# power_supply.net
KiCad netlist of a schematic drawn in EAGLE
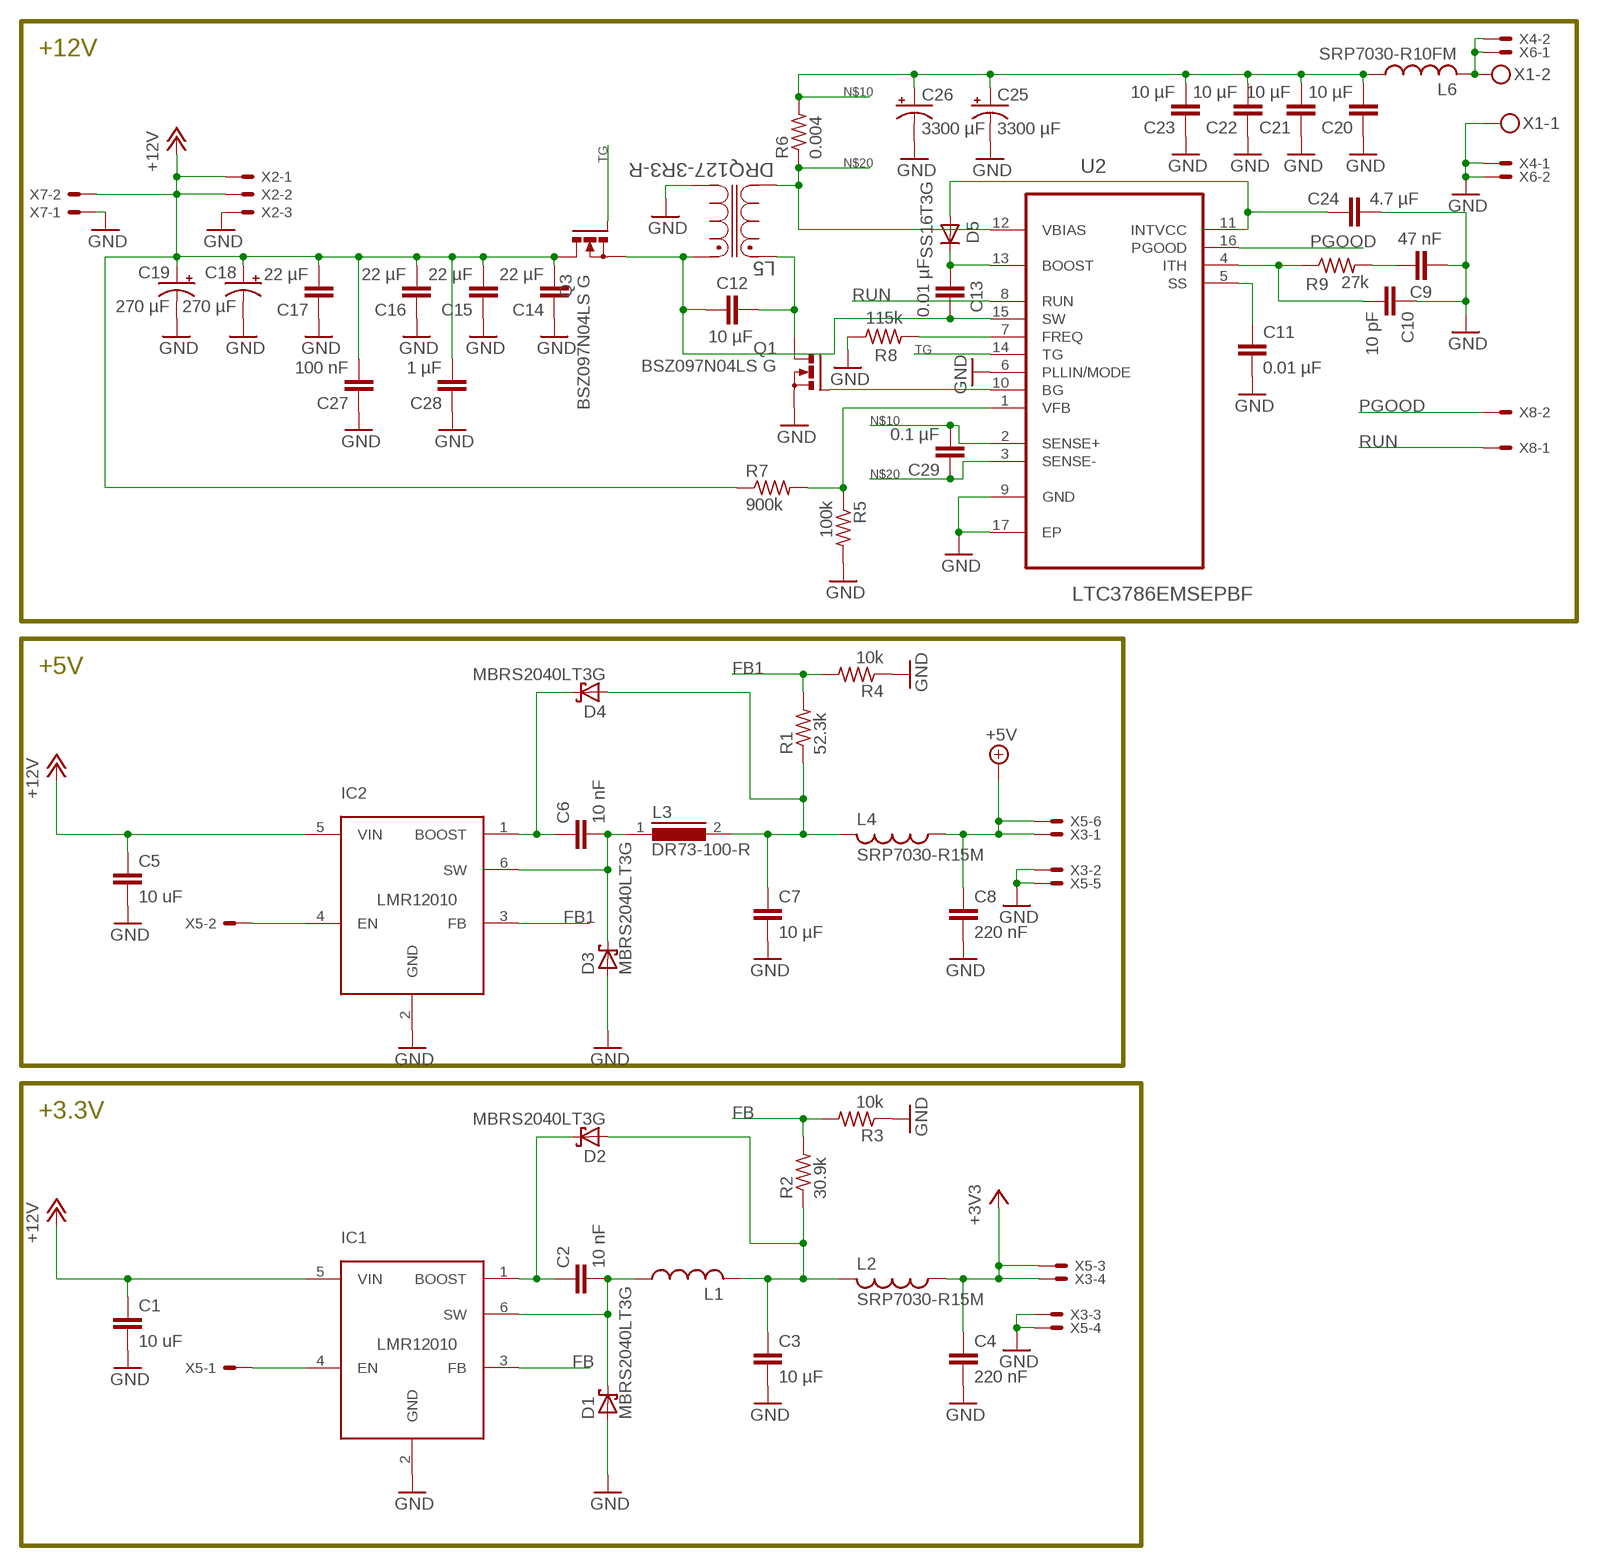
[diagram p0: schematic, sheet 1]

(export (version "E")
  (design (tool "Eeschema 10.0.6"))
  (components
    (comp (ref "C1")
      (value "10 uF")
      (footprint "eagle-import:C0805")
      (libsource (lib "eagle-import") (part "C-EUC0805"))
    )
    (comp (ref "C2")
      (value "10 nF")
      (footprint "eagle-import:C0805")
      (libsource (lib "eagle-import") (part "C-EUC0805"))
    )
    (comp (ref "C3")
      (value "10 µF")
      (footprint "eagle-import:C0805")
      (libsource (lib "eagle-import") (part "C-EUC0805"))
    )
    (comp (ref "C4")
      (value "220 nF")
      (footprint "eagle-import:C0805")
      (libsource (lib "eagle-import") (part "C-EUC0805"))
    )
    (comp (ref "C5")
      (value "10 uF")
      (footprint "eagle-import:C0805")
      (libsource (lib "eagle-import") (part "C-EUC0805"))
    )
    (comp (ref "C6")
      (value "10 nF")
      (footprint "eagle-import:C0805")
      (libsource (lib "eagle-import") (part "C-EUC0805"))
    )
    (comp (ref "C7")
      (value "10 µF")
      (footprint "eagle-import:C0805")
      (libsource (lib "eagle-import") (part "C-EUC0805"))
    )
    (comp (ref "C8")
      (value "220 nF")
      (footprint "eagle-import:C0805")
      (libsource (lib "eagle-import") (part "C-EUC0805"))
    )
    (comp (ref "C9")
      (value "47 nF")
      (footprint "eagle-import:C0805")
      (libsource (lib "eagle-import") (part "C-EUC0805"))
    )
    (comp (ref "C10")
      (value "10 pF")
      (footprint "eagle-import:C0805")
      (libsource (lib "eagle-import") (part "C-EUC0805"))
    )
    (comp (ref "C11")
      (value "0.01 µF")
      (footprint "eagle-import:C0805")
      (libsource (lib "eagle-import") (part "C-EUC0805"))
    )
    (comp (ref "C12")
      (value "10 µF")
      (footprint "eagle-import:C1210")
      (libsource (lib "eagle-import") (part "C-EUC1210"))
    )
    (comp (ref "C13")
      (value "0.01 µF")
      (footprint "eagle-import:C0805")
      (libsource (lib "eagle-import") (part "C-EUC0805"))
    )
    (comp (ref "C14")
      (value "22 µF")
      (footprint "eagle-import:C1210")
      (libsource (lib "eagle-import") (part "C-EUC1210"))
    )
    (comp (ref "C15")
      (value "22 µF")
      (footprint "eagle-import:C1210")
      (libsource (lib "eagle-import") (part "C-EUC1210"))
    )
    (comp (ref "C16")
      (value "22 µF")
      (footprint "eagle-import:C1210")
      (libsource (lib "eagle-import") (part "C-EUC1210"))
    )
    (comp (ref "C17")
      (value "22 µF")
      (footprint "eagle-import:C1210")
      (libsource (lib "eagle-import") (part "C-EUC1210"))
    )
    (comp (ref "C18")
      (value "270 µF")
      (footprint "eagle-import:E3,5-8")
      (libsource (lib "eagle-import") (part "CPOL-USE3.5-8"))
    )
    (comp (ref "C19")
      (value "270 µF")
      (footprint "eagle-import:E3,5-8")
      (libsource (lib "eagle-import") (part "CPOL-USE3.5-8"))
    )
    (comp (ref "C20")
      (value "10 µF")
      (footprint "eagle-import:C1210")
      (libsource (lib "eagle-import") (part "C-EUC1210"))
    )
    (comp (ref "C21")
      (value "10 µF")
      (footprint "eagle-import:C1210")
      (libsource (lib "eagle-import") (part "C-EUC1210"))
    )
    (comp (ref "C22")
      (value "10 µF")
      (footprint "eagle-import:C1210")
      (libsource (lib "eagle-import") (part "C-EUC1210"))
    )
    (comp (ref "C23")
      (value "10 µF")
      (footprint "eagle-import:C1210")
      (libsource (lib "eagle-import") (part "C-EUC1210"))
    )
    (comp (ref "C24")
      (value "4.7 µF")
      (footprint "eagle-import:C0805")
      (libsource (lib "eagle-import") (part "C-EUC0805"))
    )
    (comp (ref "C25")
      (value "3300 µF")
      (footprint "eagle-import:E7,5-16")
      (libsource (lib "eagle-import") (part "CPOL-USE7.5-16"))
    )
    (comp (ref "C26")
      (value "3300 µF")
      (footprint "eagle-import:E7,5-16")
      (libsource (lib "eagle-import") (part "CPOL-USE7.5-16"))
    )
    (comp (ref "C27")
      (value "100 nF")
      (footprint "eagle-import:C0805")
      (libsource (lib "eagle-import") (part "C-EUC0805"))
    )
    (comp (ref "C28")
      (value "1 µF")
      (footprint "eagle-import:C0805")
      (libsource (lib "eagle-import") (part "C-EUC0805"))
    )
    (comp (ref "C29")
      (value "0.1 µF")
      (footprint "eagle-import:C0805")
      (libsource (lib "eagle-import") (part "C-EUC0805"))
    )
    (comp (ref "D1")
      (value "MBRS2040LT3G")
      (footprint "eagle-import:SMB")
      (libsource (lib "eagle-import") (part "MBRS130LT3"))
    )
    (comp (ref "D2")
      (value "MBRS2040LT3G")
      (footprint "eagle-import:SMB")
      (libsource (lib "eagle-import") (part "MBRS130LT3"))
    )
    (comp (ref "D3")
      (value "MBRS2040LT3G")
      (footprint "eagle-import:SMB")
      (libsource (lib "eagle-import") (part "MBRS130LT3"))
    )
    (comp (ref "D4")
      (value "MBRS2040LT3G")
      (footprint "eagle-import:SMB")
      (libsource (lib "eagle-import") (part "MBRS130LT3"))
    )
    (comp (ref "D5")
      (value "SS16T3G")
      (footprint "eagle-import:DO-214AC")
      (libsource (lib "eagle-import") (part "DIODE-DO-214AC"))
    )
    (comp (ref "IC1")
      (value "LMR12010")
      (footprint "eagle-import:SOT23-6L")
      (libsource (lib "eagle-import") (part "LMR12010"))
    )
    (comp (ref "IC2")
      (value "LMR12010")
      (footprint "eagle-import:SOT23-6L")
      (libsource (lib "eagle-import") (part "LMR12010"))
    )
    (comp (ref "L1")
      (value "SLF7045T-100M1R3-PF")
      (footprint "eagle-import:SLF7045")
      (libsource (lib "eagle-import") (part "L-USSLF7045"))
    )
    (comp (ref "L2")
      (value "SRP7030-R15M")
      (footprint "eagle-import:SRP7030")
      (libsource (lib "eagle-import") (part "L-USSRP7030"))
    )
    (comp (ref "L3")
      (value "DR73-100-R")
      (footprint "eagle-import:DR73")
      (libsource (lib "eagle-import") (part "DR73"))
    )
    (comp (ref "L4")
      (value "SRP7030-R15M")
      (footprint "eagle-import:SRP7030")
      (libsource (lib "eagle-import") (part "L-USSRP7030"))
    )
    (comp (ref "L5")
      (value "DRQ127-3R3-R")
      (footprint "eagle-import:INDM125125X800N")
      (fields (field (name "MPN") "DRQ127-100-R") (field (name "TOLERANCE") "±20%"))
      (libsource (lib "eagle-import") (part "DRQ127-100-R"))
    )
    (comp (ref "L6")
      (value "SRP7030-R10FM")
      (footprint "eagle-import:SRP7030")
      (libsource (lib "eagle-import") (part "L-USSRP7030"))
    )
    (comp (ref "Q1")
      (value "BSZ097N04LS G")
      (footprint "eagle-import:PG-TDSON-8")
      (libsource (lib "eagle-import") (part "BSZ105N04NS"))
    )
    (comp (ref "Q3")
      (value "BSZ097N04LS G")
      (footprint "eagle-import:PG-TDSON-8")
      (libsource (lib "eagle-import") (part "BSZ105N04NS"))
    )
    (comp (ref "R1")
      (value "52.3k")
      (footprint "eagle-import:R0805")
      (libsource (lib "eagle-import") (part "R-US_R0805"))
    )
    (comp (ref "R2")
      (value "30.9k")
      (footprint "eagle-import:R0805")
      (libsource (lib "eagle-import") (part "R-US_R0805"))
    )
    (comp (ref "R3")
      (value "10k")
      (footprint "eagle-import:R0805")
      (libsource (lib "eagle-import") (part "R-US_R0805"))
    )
    (comp (ref "R4")
      (value "10k")
      (footprint "eagle-import:R0805")
      (libsource (lib "eagle-import") (part "R-US_R0805"))
    )
    (comp (ref "R5")
      (value "100k")
      (footprint "eagle-import:R0805")
      (libsource (lib "eagle-import") (part "R-US_R0805"))
    )
    (comp (ref "R6")
      (value "0.004")
      (footprint "eagle-import:R2512")
      (libsource (lib "eagle-import") (part "R-US_R2512"))
    )
    (comp (ref "R7")
      (value "900k")
      (footprint "eagle-import:R0805")
      (libsource (lib "eagle-import") (part "R-US_R0805"))
    )
    (comp (ref "R8")
      (value "115k")
      (footprint "eagle-import:R0805")
      (libsource (lib "eagle-import") (part "R-US_R0805"))
    )
    (comp (ref "R9")
      (value "27k")
      (footprint "eagle-import:R0805")
      (libsource (lib "eagle-import") (part "R-US_R0805"))
    )
    (comp (ref "U2")
      (value "LTC3786EMSEPBF")
      (footprint "eagle-import:SOP50P690X110-17N")
      (fields (field (name "MPN") "LTC3786EMSE#PBF"))
      (libsource (lib "eagle-import") (part "LTC3786EMSEPBF"))
    )
    (comp (ref "X1")
      (value "MKDSN1,5/2-5,08")
      (footprint "eagle-import:MKDSN1,5_2-5,08")
      (fields (field (name "MPN") "MKDSN 1,5/2-5.08"))
      (libsource (lib "eagle-import") (part "MKDSN1,5/2-5,08"))
    )
    (comp (ref "X2")
      (value "KK-156-3")
      (footprint "eagle-import:KK-156-3")
      (libsource (lib "eagle-import") (part "KK-156-3"))
    )
    (comp (ref "X3")
      (value "KK-156-4")
      (footprint "eagle-import:KK-156-4")
      (libsource (lib "eagle-import") (part "KK-156-4"))
    )
    (comp (ref "X4")
      (value "KK-156-2")
      (footprint "eagle-import:KK-156-2")
      (libsource (lib "eagle-import") (part "KK-156-2"))
    )
    (comp (ref "X5")
      (value "C-GRID-06-70543")
      (footprint "eagle-import:70543-06")
      (libsource (lib "eagle-import") (part "C-GRID-06-70543"))
    )
    (comp (ref "X6")
      (value "C-GRID-02-70543")
      (footprint "eagle-import:70543-02")
      (libsource (lib "eagle-import") (part "C-GRID-02-70543"))
    )
    (comp (ref "X7")
      (value "C-GRID-02-70543")
      (footprint "eagle-import:70543-02")
      (fields (field (name "OC_FARNELL") "unknown") (field (name "OC_NEWARK") "unknown"))
      (libsource (lib "eagle-import") (part "C-GRID-02-70543"))
    )
    (comp (ref "X8")
      (value "C-GRID-02-70543")
      (footprint "eagle-import:70543-02")
      (libsource (lib "eagle-import") (part "C-GRID-02-70543"))
    )
  )
  (nets
    (net (code "1") (name "+3V3") (class "Default")
      (node (ref "C4") (pin "1") (pinfunction "1_1") (pintype "passive"))
      (node (ref "L2") (pin "1") (pinfunction "1_1") (pintype "passive"))
      (node (ref "X3") (pin "4") (pinfunction "S_4") (pintype "passive"))
      (node (ref "X5") (pin "3") (pinfunction "S_3") (pintype "passive"))
    )
    (net (code "2") (name "+5V") (class "Default")
      (node (ref "C8") (pin "1") (pinfunction "1_1") (pintype "passive"))
      (node (ref "L4") (pin "1") (pinfunction "1_1") (pintype "passive"))
      (node (ref "X3") (pin "1") (pinfunction "S_1") (pintype "passive"))
      (node (ref "X5") (pin "6") (pinfunction "S_6") (pintype "passive"))
    )
    (net (code "3") (name "+12V") (class "Default")
      (node (ref "C1") (pin "1") (pinfunction "1_1") (pintype "passive"))
      (node (ref "C14") (pin "2") (pinfunction "2_2") (pintype "passive"))
      (node (ref "C15") (pin "2") (pinfunction "2_2") (pintype "passive"))
      (node (ref "C16") (pin "2") (pinfunction "2_2") (pintype "passive"))
      (node (ref "C17") (pin "2") (pinfunction "2_2") (pintype "passive"))
      (node (ref "C18") (pin "+") (pinfunction "+_+") (pintype "passive"))
      (node (ref "C19") (pin "+") (pinfunction "+_+") (pintype "passive"))
      (node (ref "C27") (pin "2") (pinfunction "2_2") (pintype "passive"))
      (node (ref "C28") (pin "2") (pinfunction "2_2") (pintype "passive"))
      (node (ref "C5") (pin "1") (pinfunction "1_1") (pintype "passive"))
      (node (ref "IC1") (pin "5") (pinfunction "VIN_5") (pintype "bidirectional"))
      (node (ref "IC2") (pin "5") (pinfunction "VIN_5") (pintype "bidirectional"))
      (node (ref "Q3") (pin "5") (pinfunction "D_5") (pintype "passive"))
      (node (ref "Q3") (pin "6") (pinfunction "D_6") (pintype "passive"))
      (node (ref "Q3") (pin "7") (pinfunction "D_7") (pintype "passive"))
      (node (ref "Q3") (pin "8") (pinfunction "D_8") (pintype "passive"))
      (node (ref "Q3") (pin "TH") (pinfunction "D_TH") (pintype "passive"))
      (node (ref "R7") (pin "1") (pinfunction "1_1") (pintype "passive"))
      (node (ref "X2") (pin "1") (pinfunction "S_1") (pintype "passive"))
      (node (ref "X2") (pin "2") (pinfunction "S_2") (pintype "passive"))
      (node (ref "X7") (pin "2") (pinfunction "S_2") (pintype "passive"))
    )
    (net (code "4") (name "/FB") (class "Default")
      (node (ref "IC1") (pin "3") (pinfunction "FB_3") (pintype "bidirectional"))
      (node (ref "R2") (pin "2") (pinfunction "2_2") (pintype "passive"))
      (node (ref "R3") (pin "2") (pinfunction "2_2") (pintype "passive"))
    )
    (net (code "5") (name "/FB1") (class "Default")
      (node (ref "IC2") (pin "3") (pinfunction "FB_3") (pintype "bidirectional"))
      (node (ref "R1") (pin "2") (pinfunction "2_2") (pintype "passive"))
      (node (ref "R4") (pin "2") (pinfunction "2_2") (pintype "passive"))
    )
    (net (code "6") (name "/N$10") (class "Default")
      (node (ref "C20") (pin "2") (pinfunction "2_2") (pintype "passive"))
      (node (ref "C21") (pin "2") (pinfunction "2_2") (pintype "passive"))
      (node (ref "C22") (pin "2") (pinfunction "2_2") (pintype "passive"))
      (node (ref "C23") (pin "2") (pinfunction "2_2") (pintype "passive"))
      (node (ref "C25") (pin "+") (pinfunction "+_+") (pintype "passive"))
      (node (ref "C26") (pin "+") (pinfunction "+_+") (pintype "passive"))
      (node (ref "C29") (pin "2") (pinfunction "2_2") (pintype "passive"))
      (node (ref "L6") (pin "1") (pinfunction "1_1") (pintype "passive"))
      (node (ref "R6") (pin "2") (pinfunction "2_2") (pintype "passive"))
      (node (ref "U2") (pin "2") (pinfunction "SENSE+_2") (pintype "input"))
    )
    (net (code "7") (name "/N$20") (class "Default")
      (node (ref "C29") (pin "1") (pinfunction "1_1") (pintype "passive"))
      (node (ref "L5") (pin "3") (pinfunction "3_3") (pintype "passive"))
      (node (ref "R6") (pin "1") (pinfunction "1_1") (pintype "passive"))
      (node (ref "U2") (pin "12") (pinfunction "VBIAS_12") (pintype "power_in"))
      (node (ref "U2") (pin "3") (pinfunction "SENSE-_3") (pintype "input"))
    )
    (net (code "8") (name "/PGOOD") (class "Default")
      (node (ref "U2") (pin "16") (pinfunction "PGOOD_16") (pintype "output"))
      (node (ref "X8") (pin "2") (pinfunction "S_2") (pintype "passive"))
    )
    (net (code "9") (name "/RUN") (class "Default")
      (node (ref "U2") (pin "8") (pinfunction "RUN_8") (pintype "input"))
      (node (ref "X8") (pin "1") (pinfunction "S_1") (pintype "passive"))
    )
    (net (code "10") (name "/TG") (class "Default")
      (node (ref "Q3") (pin "4") (pinfunction "G_4") (pintype "passive"))
      (node (ref "U2") (pin "14") (pinfunction "TG_14") (pintype "input"))
    )
    (net (code "11") (name "GND") (class "Default")
      (node (ref "C1") (pin "2") (pinfunction "2_2") (pintype "passive"))
      (node (ref "C10") (pin "1") (pinfunction "1_1") (pintype "passive"))
      (node (ref "C11") (pin "2") (pinfunction "2_2") (pintype "passive"))
      (node (ref "C14") (pin "1") (pinfunction "1_1") (pintype "passive"))
      (node (ref "C15") (pin "1") (pinfunction "1_1") (pintype "passive"))
      (node (ref "C16") (pin "1") (pinfunction "1_1") (pintype "passive"))
      (node (ref "C17") (pin "1") (pinfunction "1_1") (pintype "passive"))
      (node (ref "C18") (pin "-") (pinfunction "-_-") (pintype "passive"))
      (node (ref "C19") (pin "-") (pinfunction "-_-") (pintype "passive"))
      (node (ref "C20") (pin "1") (pinfunction "1_1") (pintype "passive"))
      (node (ref "C21") (pin "1") (pinfunction "1_1") (pintype "passive"))
      (node (ref "C22") (pin "1") (pinfunction "1_1") (pintype "passive"))
      (node (ref "C23") (pin "1") (pinfunction "1_1") (pintype "passive"))
      (node (ref "C24") (pin "2") (pinfunction "2_2") (pintype "passive"))
      (node (ref "C25") (pin "-") (pinfunction "-_-") (pintype "passive"))
      (node (ref "C26") (pin "-") (pinfunction "-_-") (pintype "passive"))
      (node (ref "C27") (pin "1") (pinfunction "1_1") (pintype "passive"))
      (node (ref "C28") (pin "1") (pinfunction "1_1") (pintype "passive"))
      (node (ref "C3") (pin "2") (pinfunction "2_2") (pintype "passive"))
      (node (ref "C4") (pin "2") (pinfunction "2_2") (pintype "passive"))
      (node (ref "C5") (pin "2") (pinfunction "2_2") (pintype "passive"))
      (node (ref "C7") (pin "2") (pinfunction "2_2") (pintype "passive"))
      (node (ref "C8") (pin "2") (pinfunction "2_2") (pintype "passive"))
      (node (ref "C9") (pin "2") (pinfunction "2_2") (pintype "passive"))
      (node (ref "D1") (pin "A") (pinfunction "A_A") (pintype "passive"))
      (node (ref "D3") (pin "A") (pinfunction "A_A") (pintype "passive"))
      (node (ref "IC1") (pin "2") (pinfunction "GND_2") (pintype "bidirectional"))
      (node (ref "IC2") (pin "2") (pinfunction "GND_2") (pintype "bidirectional"))
      (node (ref "L5") (pin "4") (pinfunction "4_4") (pintype "passive"))
      (node (ref "Q1") (pin "1") (pinfunction "S_1") (pintype "passive"))
      (node (ref "Q1") (pin "2") (pinfunction "S_2") (pintype "passive"))
      (node (ref "Q1") (pin "3") (pinfunction "S_3") (pintype "passive"))
      (node (ref "R3") (pin "1") (pinfunction "1_1") (pintype "passive"))
      (node (ref "R4") (pin "1") (pinfunction "1_1") (pintype "passive"))
      (node (ref "R5") (pin "2") (pinfunction "2_2") (pintype "passive"))
      (node (ref "R8") (pin "1") (pinfunction "1_1") (pintype "passive"))
      (node (ref "U2") (pin "17") (pinfunction "EP_17") (pintype "passive"))
      (node (ref "U2") (pin "6") (pinfunction "PLLIN/MODE_6") (pintype "input"))
      (node (ref "U2") (pin "9") (pinfunction "GND_9") (pintype "passive"))
      (node (ref "X1") (pin "1") (pinfunction "KL_1") (pintype "passive"))
      (node (ref "X2") (pin "3") (pinfunction "S_3") (pintype "passive"))
      (node (ref "X3") (pin "2") (pinfunction "S_2") (pintype "passive"))
      (node (ref "X3") (pin "3") (pinfunction "S_3") (pintype "passive"))
      (node (ref "X4") (pin "1") (pinfunction "S_1") (pintype "passive"))
      (node (ref "X5") (pin "4") (pinfunction "S_4") (pintype "passive"))
      (node (ref "X5") (pin "5") (pinfunction "S_5") (pintype "passive"))
      (node (ref "X6") (pin "2") (pinfunction "S_2") (pintype "passive"))
      (node (ref "X7") (pin "1") (pinfunction "S_1") (pintype "passive"))
    )
    (net (code "12") (name "Net-(C3-Pad1)") (class "Default")
      (node (ref "C3") (pin "1") (pinfunction "1_1") (pintype "passive"))
      (node (ref "D2") (pin "A") (pinfunction "A_A") (pintype "passive"))
      (node (ref "L1") (pin "2") (pinfunction "2_2") (pintype "passive"))
      (node (ref "L2") (pin "2") (pinfunction "2_2") (pintype "passive"))
      (node (ref "R2") (pin "1") (pinfunction "1_1") (pintype "passive"))
    )
    (net (code "13") (name "Net-(C7-Pad1)") (class "Default")
      (node (ref "C7") (pin "1") (pinfunction "1_1") (pintype "passive"))
      (node (ref "D4") (pin "A") (pinfunction "A_A") (pintype "passive"))
      (node (ref "L3") (pin "2") (pinfunction "2_2") (pintype "passive"))
      (node (ref "L4") (pin "2") (pinfunction "2_2") (pintype "passive"))
      (node (ref "R1") (pin "1") (pinfunction "1_1") (pintype "passive"))
    )
    (net (code "14") (name "Net-(C9-Pad1)") (class "Default")
      (node (ref "C9") (pin "1") (pinfunction "1_1") (pintype "passive"))
      (node (ref "R9") (pin "2") (pinfunction "2_2") (pintype "passive"))
    )
    (net (code "15") (name "Net-(C12-Pad1)") (class "Default")
      (node (ref "C12") (pin "1") (pinfunction "1_1") (pintype "passive"))
      (node (ref "L5") (pin "1") (pinfunction "1_1") (pintype "passive"))
      (node (ref "Q1") (pin "5") (pinfunction "D_5") (pintype "passive"))
      (node (ref "Q1") (pin "6") (pinfunction "D_6") (pintype "passive"))
      (node (ref "Q1") (pin "7") (pinfunction "D_7") (pintype "passive"))
      (node (ref "Q1") (pin "8") (pinfunction "D_8") (pintype "passive"))
      (node (ref "Q1") (pin "TH") (pinfunction "D_TH") (pintype "passive"))
    )
    (net (code "16") (name "Net-(IC1-BOOST)") (class "Default")
      (node (ref "C2") (pin "1") (pinfunction "1_1") (pintype "passive"))
      (node (ref "D2") (pin "C") (pinfunction "C_C") (pintype "passive"))
      (node (ref "IC1") (pin "1") (pinfunction "BOOST_1") (pintype "bidirectional"))
    )
    (net (code "17") (name "Net-(IC1-EN)") (class "Default")
      (node (ref "IC1") (pin "4") (pinfunction "EN_4") (pintype "bidirectional"))
      (node (ref "X5") (pin "1") (pinfunction "S_1") (pintype "passive"))
    )
    (net (code "18") (name "Net-(IC1-SW)") (class "Default")
      (node (ref "C2") (pin "2") (pinfunction "2_2") (pintype "passive"))
      (node (ref "D1") (pin "C") (pinfunction "C_C") (pintype "passive"))
      (node (ref "IC1") (pin "6") (pinfunction "SW_6") (pintype "bidirectional"))
      (node (ref "L1") (pin "1") (pinfunction "1_1") (pintype "passive"))
    )
    (net (code "19") (name "Net-(IC2-BOOST)") (class "Default")
      (node (ref "C6") (pin "1") (pinfunction "1_1") (pintype "passive"))
      (node (ref "D4") (pin "C") (pinfunction "C_C") (pintype "passive"))
      (node (ref "IC2") (pin "1") (pinfunction "BOOST_1") (pintype "bidirectional"))
    )
    (net (code "20") (name "Net-(IC2-EN)") (class "Default")
      (node (ref "IC2") (pin "4") (pinfunction "EN_4") (pintype "bidirectional"))
      (node (ref "X5") (pin "2") (pinfunction "S_2") (pintype "passive"))
    )
    (net (code "21") (name "Net-(IC2-SW)") (class "Default")
      (node (ref "C6") (pin "2") (pinfunction "2_2") (pintype "passive"))
      (node (ref "D3") (pin "C") (pinfunction "C_C") (pintype "passive"))
      (node (ref "IC2") (pin "6") (pinfunction "SW_6") (pintype "bidirectional"))
      (node (ref "L3") (pin "1") (pinfunction "1_1") (pintype "passive"))
    )
    (net (code "22") (name "Net-(Q1-G)") (class "Default")
      (node (ref "Q1") (pin "4") (pinfunction "G_4") (pintype "passive"))
      (node (ref "U2") (pin "10") (pinfunction "BG_10") (pintype "input"))
    )
    (net (code "23") (name "Net-(U2-BOOST)") (class "Default")
      (node (ref "C13") (pin "1") (pinfunction "1_1") (pintype "passive"))
      (node (ref "D5") (pin "C") (pinfunction "C_C") (pintype "passive"))
      (node (ref "U2") (pin "13") (pinfunction "BOOST_13") (pintype "power_in"))
    )
    (net (code "24") (name "Net-(U2-FREQ)") (class "Default")
      (node (ref "R8") (pin "2") (pinfunction "2_2") (pintype "passive"))
      (node (ref "U2") (pin "7") (pinfunction "FREQ_7") (pintype "input"))
    )
    (net (code "25") (name "Net-(U2-INTVCC)") (class "Default")
      (node (ref "C24") (pin "1") (pinfunction "1_1") (pintype "passive"))
      (node (ref "D5") (pin "A") (pinfunction "A_A") (pintype "passive"))
      (node (ref "U2") (pin "11") (pinfunction "INTVCC_11") (pintype "output"))
    )
    (net (code "26") (name "Net-(U2-ITH)") (class "Default")
      (node (ref "C10") (pin "2") (pinfunction "2_2") (pintype "passive"))
      (node (ref "R9") (pin "1") (pinfunction "1_1") (pintype "passive"))
      (node (ref "U2") (pin "4") (pinfunction "ITH_4") (pintype "bidirectional"))
    )
    (net (code "27") (name "Net-(U2-SS)") (class "Default")
      (node (ref "C11") (pin "1") (pinfunction "1_1") (pintype "passive"))
      (node (ref "U2") (pin "5") (pinfunction "SS_5") (pintype "output"))
    )
    (net (code "28") (name "Net-(U2-SW)") (class "Default")
      (node (ref "C12") (pin "2") (pinfunction "2_2") (pintype "passive"))
      (node (ref "C13") (pin "2") (pinfunction "2_2") (pintype "passive"))
      (node (ref "L5") (pin "2") (pinfunction "2_2") (pintype "passive"))
      (node (ref "Q3") (pin "1") (pinfunction "S_1") (pintype "passive"))
      (node (ref "Q3") (pin "2") (pinfunction "S_2") (pintype "passive"))
      (node (ref "Q3") (pin "3") (pinfunction "S_3") (pintype "passive"))
      (node (ref "U2") (pin "15") (pinfunction "SW_15") (pintype "input"))
    )
    (net (code "29") (name "Net-(U2-VFB)") (class "Default")
      (node (ref "R5") (pin "1") (pinfunction "1_1") (pintype "passive"))
      (node (ref "R7") (pin "2") (pinfunction "2_2") (pintype "passive"))
      (node (ref "U2") (pin "1") (pinfunction "VFB_1") (pintype "input"))
    )
    (net (code "30") (name "Net-(X1B-KL)") (class "Default")
      (node (ref "L6") (pin "2") (pinfunction "2_2") (pintype "passive"))
      (node (ref "X1") (pin "2") (pinfunction "KL_2") (pintype "passive"))
      (node (ref "X4") (pin "2") (pinfunction "S_2") (pintype "passive"))
      (node (ref "X6") (pin "1") (pinfunction "S_1") (pintype "passive"))
    )
  )
)
